# RS232_485.net
KiCad netlist of a schematic drawn in Altium Designer
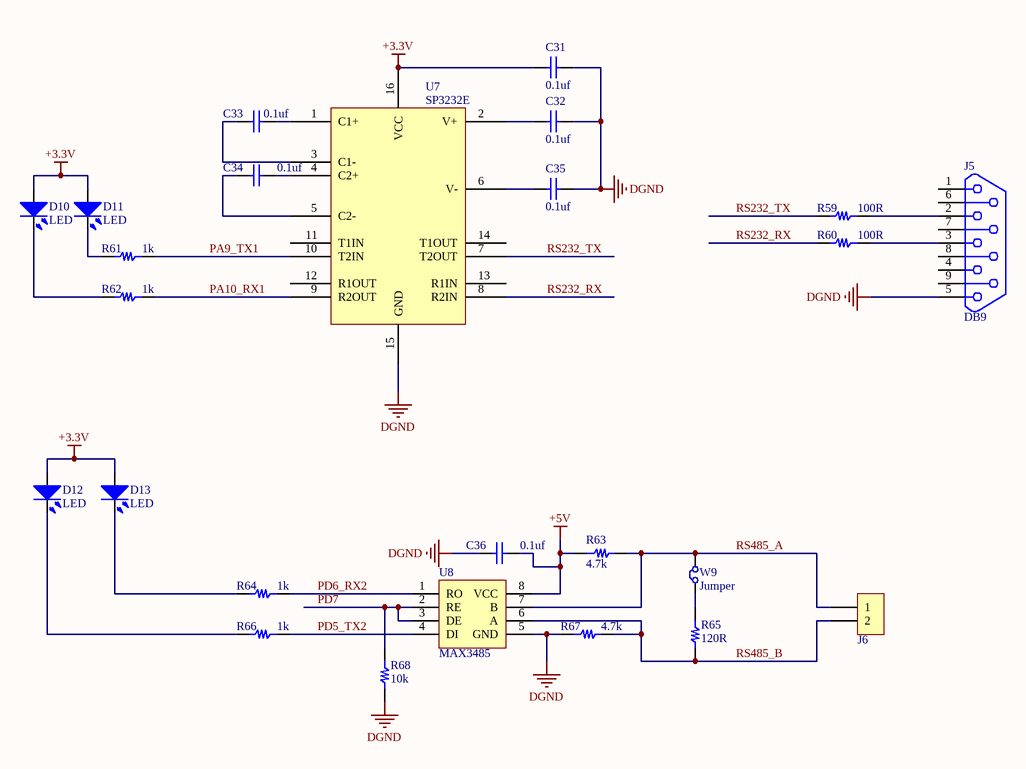
[diagram p0: RS232_485.SchDoc]

(export (version "E")
  (design (tool "Eeschema 10.0.6"))
  (components
    (comp (ref "C31")
      (value "0.1uf")
      (footprint "0805C")
      (description "贴片电容")
      (fields (field (name "PUBLISHER") "Altium Limited"))
      (libsource (lib "Device_CHT") (part "Cap"))
    )
    (comp (ref "C32")
      (value "0.1uf")
      (footprint "0805C")
      (description "贴片电容")
      (fields (field (name "PUBLISHER") "Altium Limited"))
      (libsource (lib "Device_CHT") (part "Cap"))
    )
    (comp (ref "C33")
      (value "0.1uf")
      (footprint "0805C")
      (description "贴片电容")
      (fields (field (name "PUBLISHER") "Altium Limited"))
      (libsource (lib "Device_CHT") (part "Cap"))
    )
    (comp (ref "C34")
      (value "0.1uf")
      (footprint "0805C")
      (description "贴片电容")
      (fields (field (name "PUBLISHER") "Altium Limited"))
      (libsource (lib "Device_CHT") (part "Cap"))
    )
    (comp (ref "C35")
      (value "0.1uf")
      (footprint "0805C")
      (description "贴片电容")
      (fields (field (name "PUBLISHER") "Altium Limited"))
      (libsource (lib "Device_CHT") (part "Cap"))
    )
    (comp (ref "C36")
      (value "0.1uf")
      (footprint "0805C")
      (description "贴片电容")
      (fields (field (name "PUBLISHER") "Altium Limited"))
      (libsource (lib "Device_CHT") (part "Cap"))
    )
    (comp (ref "D10")
      (value "LED")
      (footprint "0805-LED-RED")
      (description "Typical INFRARED GaAs LED")
      (fields (field (name "PUBLISHER") "Altium Limited"))
      (libsource (lib "Device_CHT") (part "LED"))
    )
    (comp (ref "D11")
      (value "LED")
      (footprint "0805-LED-RED")
      (description "Typical INFRARED GaAs LED")
      (fields (field (name "PUBLISHER") "Altium Limited"))
      (libsource (lib "Device_CHT") (part "LED"))
    )
    (comp (ref "D12")
      (value "LED")
      (footprint "0805-LED-RED")
      (description "Typical INFRARED GaAs LED")
      (fields (field (name "PUBLISHER") "Altium Limited"))
      (libsource (lib "Device_CHT") (part "LED"))
    )
    (comp (ref "D13")
      (value "LED")
      (footprint "0805-LED-RED")
      (description "Typical INFRARED GaAs LED")
      (fields (field (name "PUBLISHER") "Altium Limited"))
      (libsource (lib "Device_CHT") (part "LED"))
    )
    (comp (ref "J5") (value "DB9") (footprint "DB9RA/M") (libsource (lib "Connector_Veiko") (part "DB9")))
    (comp (ref "J6")
      (value "CON2")
      (footprint "XH2.54-2P")
      (description "Connector")
      (libsource (lib "Connector_Veiko") (part "CON2"))
    )
    (comp (ref "R59")
      (value "100R")
      (footprint "0805_small")
      (description "电阻")
      (fields (field (name "PUBLISHER") "Altium Limited"))
      (libsource (lib "Device_CHT") (part "Res"))
    )
    (comp (ref "R60")
      (value "100R")
      (footprint "0805_small")
      (description "电阻")
      (fields (field (name "PUBLISHER") "Altium Limited"))
      (libsource (lib "Device_CHT") (part "Res"))
    )
    (comp (ref "R61")
      (value "1k")
      (footprint "0805_small")
      (description "电阻")
      (fields (field (name "PUBLISHER") "Altium Limited"))
      (libsource (lib "Device_CHT") (part "Res"))
    )
    (comp (ref "R62")
      (value "1k")
      (footprint "0805_small")
      (description "电阻")
      (fields (field (name "PUBLISHER") "Altium Limited"))
      (libsource (lib "Device_CHT") (part "Res"))
    )
    (comp (ref "R63")
      (value "4.7k")
      (footprint "0805_small")
      (description "电阻")
      (fields (field (name "PUBLISHER") "Altium Limited"))
      (libsource (lib "Device_CHT") (part "Res"))
    )
    (comp (ref "R64")
      (value "1k")
      (footprint "0805_small")
      (description "电阻")
      (fields (field (name "PUBLISHER") "Altium Limited"))
      (libsource (lib "Device_CHT") (part "Res"))
    )
    (comp (ref "R65")
      (value "120R")
      (footprint "0805_small")
      (description "电阻")
      (fields (field (name "PUBLISHER") "Altium Limited"))
      (libsource (lib "Device_CHT") (part "Res"))
    )
    (comp (ref "R66")
      (value "1k")
      (footprint "0805_small")
      (description "电阻")
      (fields (field (name "PUBLISHER") "Altium Limited"))
      (libsource (lib "Device_CHT") (part "Res"))
    )
    (comp (ref "R67")
      (value "4.7k")
      (footprint "0805_small")
      (description "电阻")
      (fields (field (name "PUBLISHER") "Altium Limited"))
      (libsource (lib "Device_CHT") (part "Res"))
    )
    (comp (ref "R68")
      (value "10k")
      (footprint "0805_small")
      (description "电阻")
      (fields (field (name "PUBLISHER") "Altium Limited"))
      (libsource (lib "Device_CHT") (part "Res"))
    )
    (comp (ref "U7") (value "SP3232E") (footprint "SO-16") (libsource (lib "Device_CHT") (part "SP3232E")))
    (comp (ref "U8") (value "MAX3485") (footprint "SO-8") (libsource (lib "Device_CHT") (part "MAX3485")))
    (comp (ref "W9")
      (value "Jumper")
      (footprint "0603_jump_Pad")
      (description "Jumper Wire")
      (fields (field (name "PUBLISHER") "Altium Limited"))
      (libsource (lib "Connector_Veiko") (part "Jumper"))
    )
  )
  (nets
    (net (code "1") (name "+3.3V") (class "Default")
      (node (ref "C31") (pin "2") (pinfunction "2_2") (pintype "passive"))
      (node (ref "D10") (pin "1") (pinfunction "A_1") (pintype "passive"))
      (node (ref "D11") (pin "1") (pinfunction "A_1") (pintype "passive"))
      (node (ref "D12") (pin "1") (pinfunction "A_1") (pintype "passive"))
      (node (ref "D13") (pin "1") (pinfunction "A_1") (pintype "passive"))
      (node (ref "U7") (pin "16") (pinfunction "VCC_16") (pintype "passive"))
    )
    (net (code "2") (name "+5V") (class "Default")
      (node (ref "C36") (pin "1") (pinfunction "1_1") (pintype "passive"))
      (node (ref "R63") (pin "1") (pinfunction "1_1") (pintype "passive"))
      (node (ref "U8") (pin "8") (pinfunction "VCC_8") (pintype "passive"))
    )
    (net (code "3") (name "/PA9_TX1") (class "Default")
      (node (ref "R61") (pin "1") (pinfunction "1_1") (pintype "passive"))
      (node (ref "U7") (pin "10") (pinfunction "T2IN_10") (pintype "passive"))
    )
    (net (code "4") (name "/PA10_RX1") (class "Default")
      (node (ref "R62") (pin "1") (pinfunction "1_1") (pintype "passive"))
      (node (ref "U7") (pin "9") (pinfunction "R2OUT_9") (pintype "passive"))
    )
    (net (code "5") (name "/PD5_TX2") (class "Default")
      (node (ref "R66") (pin "1") (pinfunction "1_1") (pintype "passive"))
      (node (ref "U8") (pin "4") (pinfunction "DI_4") (pintype "passive"))
    )
    (net (code "6") (name "/PD6_RX2") (class "Default")
      (node (ref "R64") (pin "1") (pinfunction "1_1") (pintype "passive"))
      (node (ref "U8") (pin "1") (pinfunction "RO_1") (pintype "passive"))
    )
    (net (code "7") (name "/PD7") (class "Default")
      (node (ref "R68") (pin "1") (pinfunction "1_1") (pintype "passive"))
      (node (ref "U8") (pin "2") (pinfunction "RE_2") (pintype "passive"))
      (node (ref "U8") (pin "3") (pinfunction "DE_3") (pintype "passive"))
    )
    (net (code "8") (name "/RS232_RX") (class "Default")
      (node (ref "R60") (pin "2") (pinfunction "2_2") (pintype "passive"))
      (node (ref "U7") (pin "8") (pinfunction "R2IN_8") (pintype "passive"))
    )
    (net (code "9") (name "/RS232_TX") (class "Default")
      (node (ref "R59") (pin "2") (pinfunction "2_2") (pintype "passive"))
      (node (ref "U7") (pin "7") (pinfunction "T2OUT_7") (pintype "passive"))
    )
    (net (code "10") (name "/RS485_A") (class "Default")
      (node (ref "J6") (pin "1") (pinfunction "1_1") (pintype "passive"))
      (node (ref "R63") (pin "2") (pinfunction "2_2") (pintype "passive"))
      (node (ref "U8") (pin "7") (pinfunction "B_7") (pintype "passive"))
      (node (ref "W9") (pin "2") (pinfunction "C2_2") (pintype "passive"))
    )
    (net (code "11") (name "/RS485_B") (class "Default")
      (node (ref "J6") (pin "2") (pinfunction "2_2") (pintype "passive"))
      (node (ref "R65") (pin "2") (pinfunction "2_2") (pintype "passive"))
      (node (ref "R67") (pin "2") (pinfunction "2_2") (pintype "passive"))
      (node (ref "U8") (pin "6") (pinfunction "A_6") (pintype "passive"))
    )
    (net (code "12") (name "DGND") (class "Default")
      (node (ref "C31") (pin "1") (pinfunction "1_1") (pintype "passive"))
      (node (ref "C32") (pin "1") (pinfunction "1_1") (pintype "passive"))
      (node (ref "C35") (pin "1") (pinfunction "1_1") (pintype "passive"))
      (node (ref "C36") (pin "2") (pinfunction "2_2") (pintype "passive"))
      (node (ref "J5") (pin "5") (pinfunction "5_5") (pintype "passive"))
      (node (ref "R67") (pin "1") (pinfunction "1_1") (pintype "passive"))
      (node (ref "R68") (pin "2") (pinfunction "2_2") (pintype "passive"))
      (node (ref "U7") (pin "15") (pinfunction "GND_15") (pintype "passive"))
      (node (ref "U8") (pin "5") (pinfunction "GND_5") (pintype "passive"))
    )
    (net (code "13") (name "Net-(D10-K)") (class "Default")
      (node (ref "D10") (pin "2") (pinfunction "K_2") (pintype "passive"))
      (node (ref "R62") (pin "2") (pinfunction "2_2") (pintype "passive"))
    )
    (net (code "14") (name "Net-(D11-K)") (class "Default")
      (node (ref "D11") (pin "2") (pinfunction "K_2") (pintype "passive"))
      (node (ref "R61") (pin "2") (pinfunction "2_2") (pintype "passive"))
    )
    (net (code "15") (name "Net-(D12-K)") (class "Default")
      (node (ref "D12") (pin "2") (pinfunction "K_2") (pintype "passive"))
      (node (ref "R66") (pin "2") (pinfunction "2_2") (pintype "passive"))
    )
    (net (code "16") (name "Net-(D13-K)") (class "Default")
      (node (ref "D13") (pin "2") (pinfunction "K_2") (pintype "passive"))
      (node (ref "R64") (pin "2") (pinfunction "2_2") (pintype "passive"))
    )
    (net (code "17") (name "Net-(J5-Pad2)") (class "Default")
      (node (ref "J5") (pin "2") (pinfunction "2_2") (pintype "passive"))
      (node (ref "R59") (pin "1") (pinfunction "1_1") (pintype "passive"))
    )
    (net (code "18") (name "Net-(J5-Pad3)") (class "Default")
      (node (ref "J5") (pin "3") (pinfunction "3_3") (pintype "passive"))
      (node (ref "R60") (pin "1") (pinfunction "1_1") (pintype "passive"))
    )
    (net (code "19") (name "Net-(U7-C1+)") (class "Default")
      (node (ref "C33") (pin "1") (pinfunction "1_1") (pintype "passive"))
      (node (ref "U7") (pin "1") (pinfunction "C1+_1") (pintype "passive"))
    )
    (net (code "20") (name "Net-(U7-C1-)") (class "Default")
      (node (ref "C33") (pin "2") (pinfunction "2_2") (pintype "passive"))
      (node (ref "U7") (pin "3") (pinfunction "C1-_3") (pintype "passive"))
    )
    (net (code "21") (name "Net-(U7-C2+)") (class "Default")
      (node (ref "C34") (pin "1") (pinfunction "1_1") (pintype "passive"))
      (node (ref "U7") (pin "4") (pinfunction "C2+_4") (pintype "passive"))
    )
    (net (code "22") (name "Net-(U7-C2-)") (class "Default")
      (node (ref "C34") (pin "2") (pinfunction "2_2") (pintype "passive"))
      (node (ref "U7") (pin "5") (pinfunction "C2-_5") (pintype "passive"))
    )
    (net (code "23") (name "Net-(U7-V+)") (class "Default")
      (node (ref "C32") (pin "2") (pinfunction "2_2") (pintype "passive"))
      (node (ref "U7") (pin "2") (pinfunction "V+_2") (pintype "passive"))
    )
    (net (code "24") (name "Net-(U7-V-)") (class "Default")
      (node (ref "C35") (pin "2") (pinfunction "2_2") (pintype "passive"))
      (node (ref "U7") (pin "6") (pinfunction "V-_6") (pintype "passive"))
    )
    (net (code "25") (name "Net-(W9-C1)") (class "Default")
      (node (ref "R65") (pin "1") (pinfunction "1_1") (pintype "passive"))
      (node (ref "W9") (pin "1") (pinfunction "C1_1") (pintype "passive"))
    )
    (net (code "26") (name "unconnected-(J5-Pad1)") (class "Default")
      (node (ref "J5") (pin "1") (pinfunction "1_1") (pintype "passive"))
    )
    (net (code "27") (name "unconnected-(J5-Pad4)") (class "Default")
      (node (ref "J5") (pin "4") (pinfunction "4_4") (pintype "passive"))
    )
    (net (code "28") (name "unconnected-(J5-Pad6)") (class "Default")
      (node (ref "J5") (pin "6") (pinfunction "6_6") (pintype "passive"))
    )
    (net (code "29") (name "unconnected-(J5-Pad7)") (class "Default")
      (node (ref "J5") (pin "7") (pinfunction "7_7") (pintype "passive"))
    )
    (net (code "30") (name "unconnected-(J5-Pad8)") (class "Default")
      (node (ref "J5") (pin "8") (pinfunction "8_8") (pintype "passive"))
    )
    (net (code "31") (name "unconnected-(J5-Pad9)") (class "Default")
      (node (ref "J5") (pin "9") (pinfunction "9_9") (pintype "passive"))
    )
    (net (code "32") (name "unconnected-(U7-R1IN-Pad13)") (class "Default")
      (node (ref "U7") (pin "13") (pinfunction "R1IN_13") (pintype "passive"))
    )
    (net (code "33") (name "unconnected-(U7-R1OUT-Pad12)") (class "Default")
      (node (ref "U7") (pin "12") (pinfunction "R1OUT_12") (pintype "passive"))
    )
    (net (code "34") (name "unconnected-(U7-T1IN-Pad11)") (class "Default")
      (node (ref "U7") (pin "11") (pinfunction "T1IN_11") (pintype "passive"))
    )
    (net (code "35") (name "unconnected-(U7-T1OUT-Pad14)") (class "Default")
      (node (ref "U7") (pin "14") (pinfunction "T1OUT_14") (pintype "passive"))
    )
  )
)
